# schematic.net
KiCad netlist of a schematic drawn in EAGLE
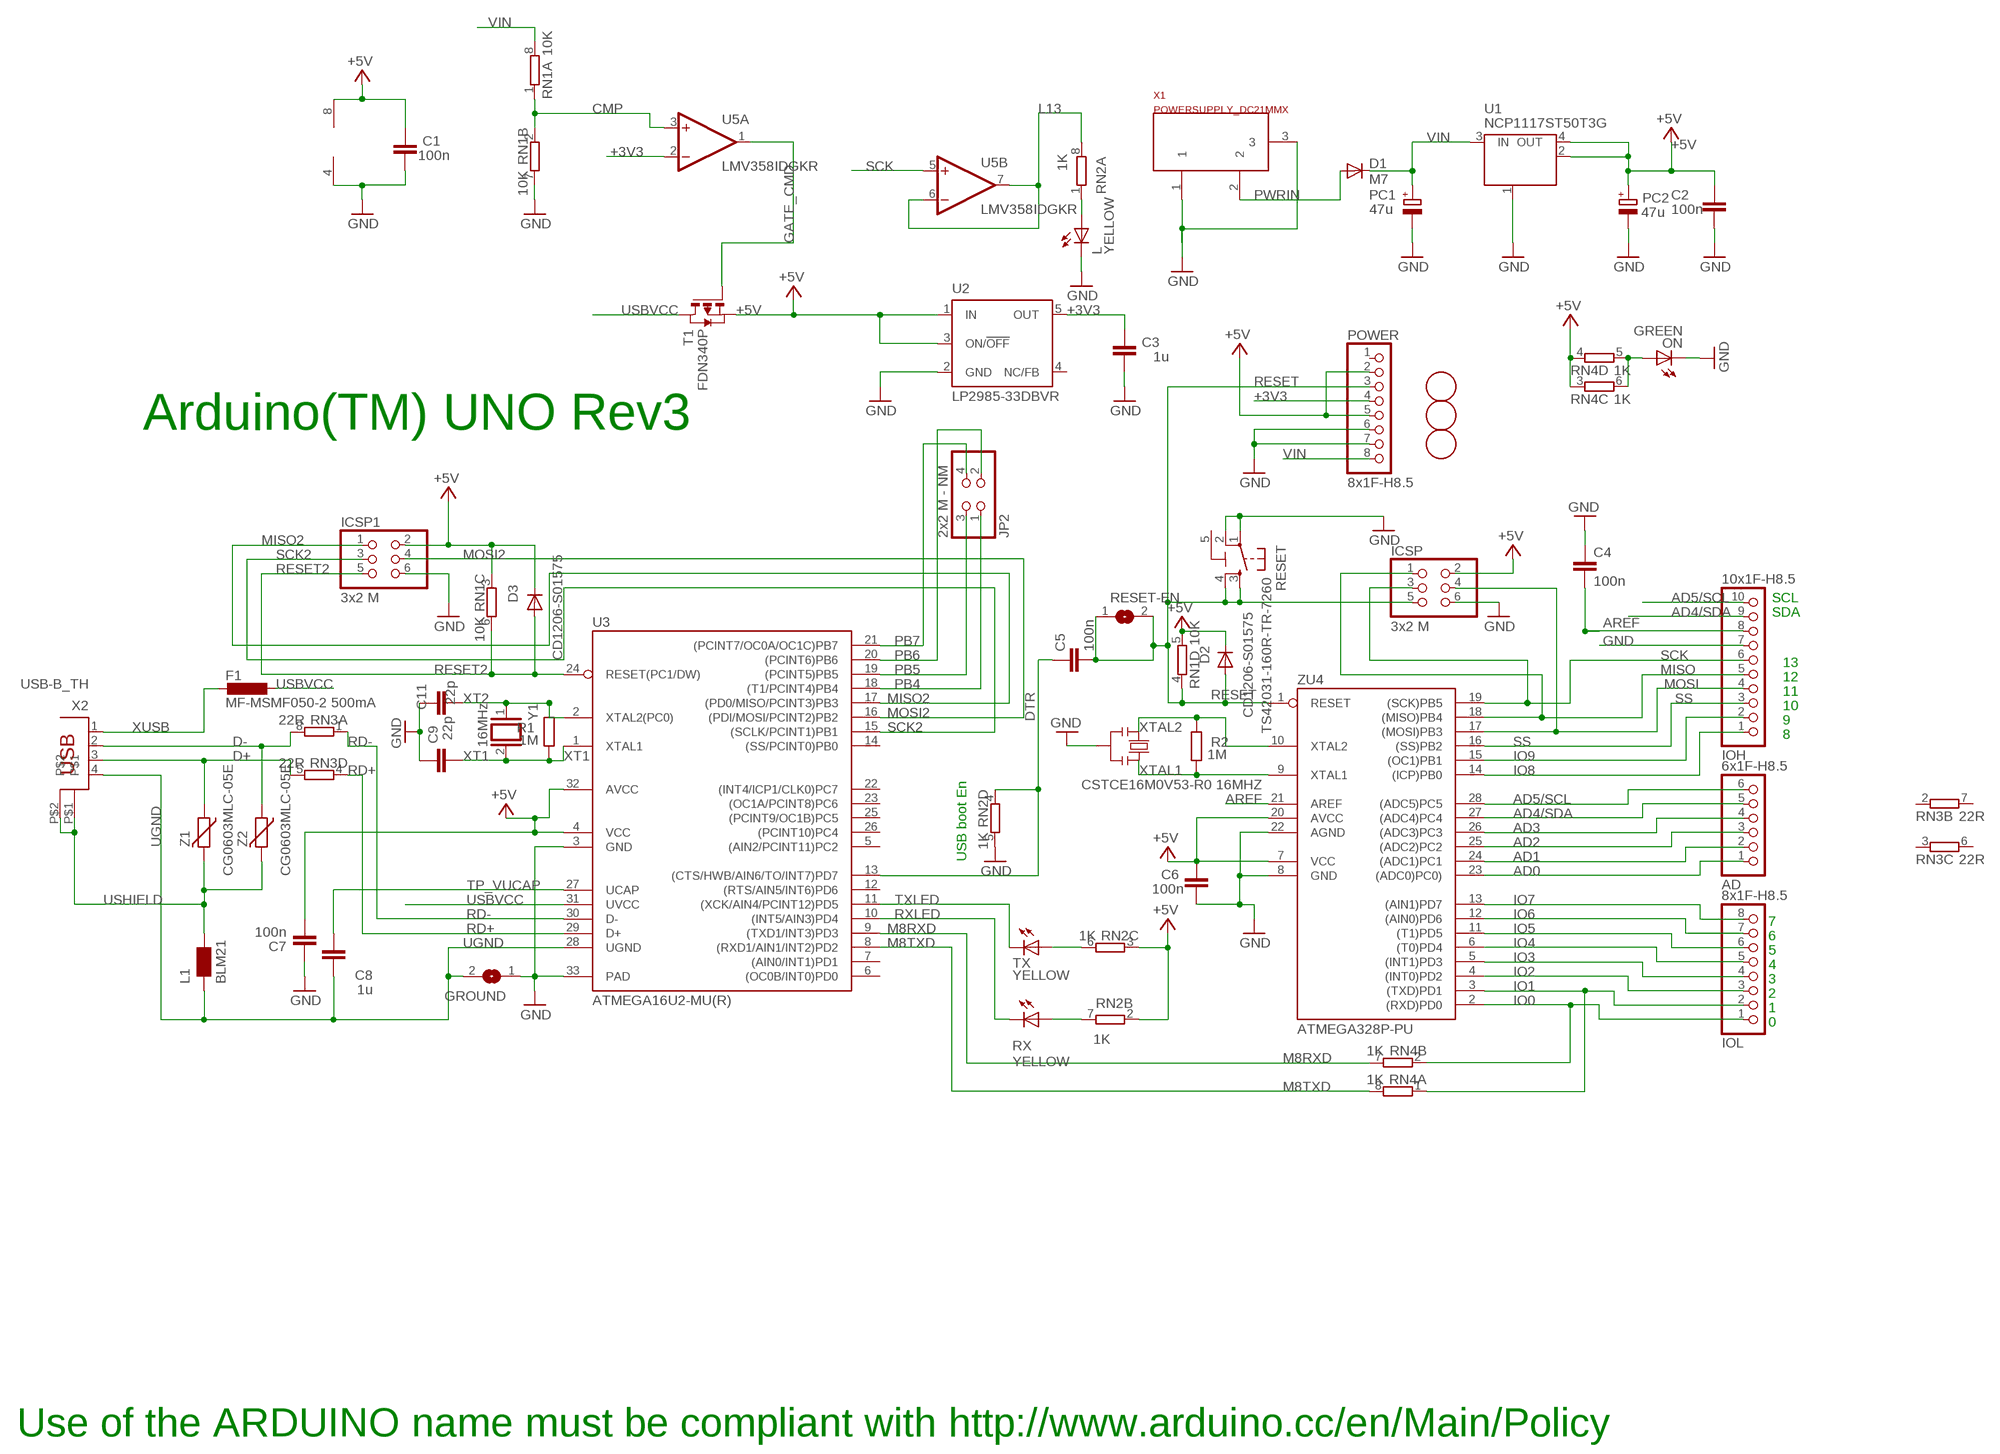
[diagram p0: schematic, sheet 1]

(export (version "E")
  (design (tool "Eeschema 10.0.6"))
  (components
    (comp (ref "AD")
      (value "6x1F-H8.5")
      (footprint "eagle-import:1X06")
      (libsource (lib "eagle-import") (part "PINHD-1X6"))
    )
    (comp (ref "C1")
      (value "100n")
      (footprint "eagle-import:C0603-ROUND")
      (libsource (lib "eagle-import") (part "C-EU0603-RND"))
    )
    (comp (ref "C2")
      (value "100n")
      (footprint "eagle-import:C0603-ROUND")
      (libsource (lib "eagle-import") (part "C-EU0603-RND"))
    )
    (comp (ref "C3")
      (value "1u")
      (footprint "eagle-import:C0603-ROUND")
      (libsource (lib "eagle-import") (part "C-EU0603-RND"))
    )
    (comp (ref "C4")
      (value "100n")
      (footprint "eagle-import:C0603-ROUND")
      (libsource (lib "eagle-import") (part "C-EU0603-RND"))
    )
    (comp (ref "C5")
      (value "100n")
      (footprint "eagle-import:C0603-ROUND")
      (libsource (lib "eagle-import") (part "C-EU0603-RND"))
    )
    (comp (ref "C6")
      (value "100n")
      (footprint "eagle-import:C0603-ROUND")
      (libsource (lib "eagle-import") (part "C-EU0603-RND"))
    )
    (comp (ref "C7")
      (value "100n")
      (footprint "eagle-import:C0603-ROUND")
      (libsource (lib "eagle-import") (part "C-EU0603-RND"))
    )
    (comp (ref "C8")
      (value "1u")
      (footprint "eagle-import:C0603-ROUND")
      (libsource (lib "eagle-import") (part "C-EU0603-RND"))
    )
    (comp (ref "C9")
      (value "22p")
      (footprint "eagle-import:C0603-ROUND")
      (libsource (lib "eagle-import") (part "C-EU0603-RND"))
    )
    (comp (ref "C11")
      (value "22p")
      (footprint "eagle-import:C0603-ROUND")
      (libsource (lib "eagle-import") (part "C-EU0603-RND"))
    )
    (comp (ref "D1")
      (value "M7")
      (footprint "eagle-import:SMB")
      (libsource (lib "eagle-import") (part "DIODE-SMB"))
    )
    (comp (ref "D2")
      (value "CD1206-S01575")
      (footprint "eagle-import:MINIMELF")
      (libsource (lib "eagle-import") (part "DIODE-MINIMELF"))
    )
    (comp (ref "D3")
      (value "CD1206-S01575")
      (footprint "eagle-import:MINIMELF")
      (libsource (lib "eagle-import") (part "DIODE-MINIMELF"))
    )
    (comp (ref "F1")
      (value "MF-MSMF050-2 500mA")
      (footprint "eagle-import:L1812")
      (libsource (lib "eagle-import") (part "L-EUL1812"))
    )
    (comp (ref "FD1")
      (value "FIDUCIALMOUNT")
      (footprint "eagle-import:FIDUCIA-MOUNT")
      (libsource (lib "eagle-import") (part "FIDUCIALMOUNT"))
    )
    (comp (ref "FD2")
      (value "FIDUCIALMOUNT")
      (footprint "eagle-import:FIDUCIA-MOUNT")
      (libsource (lib "eagle-import") (part "FIDUCIALMOUNT"))
    )
    (comp (ref "FD3")
      (value "FIDUCIALMOUNT")
      (footprint "eagle-import:FIDUCIA-MOUNT")
      (libsource (lib "eagle-import") (part "FIDUCIALMOUNT"))
    )
    (comp (ref "GROUND")
      (value "SJ")
      (footprint "eagle-import:SJ")
      (libsource (lib "eagle-import") (part "SJ"))
    )
    (comp (ref "ICSP")
      (value "3x2 M")
      (footprint "eagle-import:2X03")
      (libsource (lib "eagle-import") (part "PINHD-2X3"))
    )
    (comp (ref "ICSP1")
      (value "3x2 M")
      (footprint "eagle-import:2X03")
      (libsource (lib "eagle-import") (part "PINHD-2X3"))
    )
    (comp (ref "IOH")
      (value "10x1F-H8.5")
      (footprint "eagle-import:1X10")
      (libsource (lib "eagle-import") (part "PINHD-1X10_ARD"))
    )
    (comp (ref "IOL")
      (value "8x1F-H8.5")
      (footprint "eagle-import:1X08")
      (libsource (lib "eagle-import") (part "PINHD-1X8"))
    )
    (comp (ref "JP2")
      (value "2x2 M - NM")
      (footprint "eagle-import:2X02")
      (libsource (lib "eagle-import") (part "PINHD-2X2"))
    )
    (comp (ref "L")
      (value "YELLOW")
      (footprint "eagle-import:CHIP-LED0805")
      (libsource (lib "eagle-import") (part "LEDCHIP-LED0805"))
    )
    (comp (ref "L1")
      (value "BLM21")
      (footprint "eagle-import:0805")
      (libsource (lib "eagle-import") (part "WE-CBF_0805"))
    )
    (comp (ref "ON")
      (value "GREEN")
      (footprint "eagle-import:CHIP-LED0805")
      (libsource (lib "eagle-import") (part "LEDCHIP-LED0805"))
    )
    (comp (ref "PC1")
      (value "47u")
      (footprint "eagle-import:PANASONIC_D")
      (libsource (lib "eagle-import") (part "CPOL-EUD"))
    )
    (comp (ref "PC2")
      (value "47u")
      (footprint "eagle-import:PANASONIC_D")
      (libsource (lib "eagle-import") (part "CPOL-EUD"))
    )
    (comp (ref "POWER")
      (value "8x1F-H8.5")
      (footprint "eagle-import:1X08")
      (libsource (lib "eagle-import") (part "PINHD-1X8"))
    )
    (comp (ref "R1")
      (value "1M")
      (footprint "eagle-import:R0603-ROUND")
      (libsource (lib "eagle-import") (part "R-EU_R0603"))
    )
    (comp (ref "R2")
      (value "1M")
      (footprint "eagle-import:R0603-ROUND")
      (libsource (lib "eagle-import") (part "R-EU_R0603"))
    )
    (comp (ref "RESET")
      (value "TS42031-160R-TR-7260")
      (footprint "eagle-import:TS42")
      (libsource (lib "eagle-import") (part "TS42"))
    )
    (comp (ref "RESET-EN")
      (value "SJ")
      (footprint "eagle-import:SJ")
      (libsource (lib "eagle-import") (part "SJ"))
    )
    (comp (ref "RN1")
      (value "10K")
      (footprint "eagle-import:CAY16")
      (libsource (lib "eagle-import") (part "4R-NCAY16"))
    )
    (comp (ref "RN2")
      (value "1K")
      (footprint "eagle-import:CAY16")
      (libsource (lib "eagle-import") (part "4R-NCAY16"))
    )
    (comp (ref "RN3")
      (value "22R")
      (footprint "eagle-import:CAY16")
      (libsource (lib "eagle-import") (part "4R-NCAY16"))
    )
    (comp (ref "RN4")
      (value "1K")
      (footprint "eagle-import:CAY16")
      (libsource (lib "eagle-import") (part "4R-NCAY16"))
    )
    (comp (ref "RX")
      (value "YELLOW")
      (footprint "eagle-import:CHIP-LED0805")
      (libsource (lib "eagle-import") (part "LEDCHIP-LED0805"))
    )
    (comp (ref "T1")
      (value "FDN340P")
      (footprint "eagle-import:SOT-23")
      (libsource (lib "eagle-import") (part "PMOSSOT23"))
    )
    (comp (ref "TX")
      (value "YELLOW")
      (footprint "eagle-import:CHIP-LED0805")
      (libsource (lib "eagle-import") (part "LEDCHIP-LED0805"))
    )
    (comp (ref "U1")
      (value "NCP1117ST50T3G")
      (footprint "eagle-import:SOT223")
      (libsource (lib "eagle-import") (part "MC33269ST-3.3T3"))
    )
    (comp (ref "U2")
      (value "LP2985-33DBVR")
      (footprint "eagle-import:SOT23-DBV")
      (libsource (lib "eagle-import") (part "LP2985-XXDBVR33"))
    )
    (comp (ref "U3")
      (value "ATMEGA16U2-MU(R)")
      (footprint "eagle-import:MLF32")
      (libsource (lib "eagle-import") (part "ATMEGA16U2-MU"))
    )
    (comp (ref "U5")
      (value "LMV358IDGKR")
      (footprint "eagle-import:MSOP08")
      (libsource (lib "eagle-import") (part "LMV358?MMX"))
    )
    (comp (ref "X1")
      (value "POWERSUPPLY_DC21MMX")
      (footprint "eagle-import:POWERSUPPLY_DC-21MM")
      (libsource (lib "eagle-import") (part "POWERSUPPLY_DC21MMX"))
    )
    (comp (ref "X2")
      (value "USB-B_TH")
      (footprint "eagle-import:PN61729")
      (libsource (lib "eagle-import") (part "PN61729"))
    )
    (comp (ref "Y1")
      (value "16MHz")
      (footprint "eagle-import:QS")
      (libsource (lib "eagle-import") (part "XTAL/S"))
    )
    (comp (ref "Y2")
      (value "CSTCE16M0V53-R0 16MHZ")
      (footprint "eagle-import:RESONATOR")
      (libsource (lib "eagle-import") (part "RESONATORMU"))
    )
    (comp (ref "Z1")
      (value "CG0603MLC-05E")
      (footprint "eagle-import:CT_CN0603")
      (libsource (lib "eagle-import") (part "VARISTORCN0603"))
    )
    (comp (ref "Z2")
      (value "CG0603MLC-05E")
      (footprint "eagle-import:CT_CN0603")
      (libsource (lib "eagle-import") (part "VARISTORCN0603"))
    )
    (comp (ref "ZU4")
      (value "ATMEGA328P-PU")
      (footprint "eagle-import:DIL28-3")
      (libsource (lib "eagle-import") (part "ATMEGA328P-PU"))
    )
  )
  (nets
    (net (code "1") (name "+5V") (class "Default")
      (node (ref "C1") (pin "2") (pinfunction "2_2") (pintype "passive"))
      (node (ref "C2") (pin "2") (pinfunction "2_2") (pintype "passive"))
      (node (ref "C6") (pin "2") (pinfunction "2_2") (pintype "passive"))
      (node (ref "C7") (pin "1") (pinfunction "1_1") (pintype "passive"))
      (node (ref "D2") (pin "C") (pinfunction "C_C") (pintype "passive"))
      (node (ref "D3") (pin "C") (pinfunction "C_C") (pintype "passive"))
      (node (ref "ICSP") (pin "2") (pinfunction "2_2") (pintype "passive"))
      (node (ref "ICSP1") (pin "2") (pinfunction "2_2") (pintype "passive"))
      (node (ref "PC2") (pin "+") (pinfunction "+_+") (pintype "passive"))
      (node (ref "POWER") (pin "2") (pinfunction "2_2") (pintype "passive"))
      (node (ref "POWER") (pin "5") (pinfunction "5_5") (pintype "passive"))
      (node (ref "RN1") (pin "3") (pinfunction "1_3") (pintype "passive"))
      (node (ref "RN1") (pin "5") (pinfunction "2_5") (pintype "passive"))
      (node (ref "RN2") (pin "2") (pinfunction "1_2") (pintype "passive"))
      (node (ref "RN2") (pin "3") (pinfunction "1_3") (pintype "passive"))
      (node (ref "RN4") (pin "3") (pinfunction "1_3") (pintype "passive"))
      (node (ref "RN4") (pin "4") (pinfunction "1_4") (pintype "passive"))
      (node (ref "T1") (pin "2") (pinfunction "S_2") (pintype "passive"))
      (node (ref "U1") (pin "2") (pinfunction "OUT_2") (pintype "passive"))
      (node (ref "U1") (pin "4") (pinfunction "OUT_4") (pintype "passive"))
      (node (ref "U2") (pin "1") (pinfunction "IN_1") (pintype "input"))
      (node (ref "U2") (pin "3") (pinfunction "ON/~{OFF}_3") (pintype "input"))
      (node (ref "U3") (pin "32") (pinfunction "AVCC_32") (pintype "power_in"))
      (node (ref "U3") (pin "4") (pinfunction "VCC_4") (pintype "power_in"))
      (node (ref "U5") (pin "8") (pinfunction "V+_8") (pintype "power_in"))
      (node (ref "ZU4") (pin "20") (pinfunction "AVCC_20") (pintype "power_in"))
      (node (ref "ZU4") (pin "7") (pinfunction "VCC_7") (pintype "power_in"))
    )
    (net (code "2") (name "/+3V3") (class "Default")
      (node (ref "C3") (pin "2") (pinfunction "2_2") (pintype "passive"))
      (node (ref "POWER") (pin "4") (pinfunction "4_4") (pintype "passive"))
      (node (ref "U2") (pin "5") (pinfunction "OUT_5") (pintype "passive"))
      (node (ref "U5") (pin "2") (pinfunction "-IN_2") (pintype "input"))
    )
    (net (code "3") (name "/5-GND") (class "Default")
      (node (ref "RESET") (pin "5") (pinfunction "5-GND_5") (pintype "power_in"))
    )
    (net (code "4") (name "/AD0") (class "Default")
      (node (ref "AD") (pin "1") (pinfunction "1_1") (pintype "passive"))
      (node (ref "ZU4") (pin "23") (pinfunction "(ADC0)PC0)_23") (pintype "bidirectional"))
    )
    (net (code "5") (name "/AD1") (class "Default")
      (node (ref "AD") (pin "2") (pinfunction "2_2") (pintype "passive"))
      (node (ref "ZU4") (pin "24") (pinfunction "(ADC1)PC1_24") (pintype "bidirectional"))
    )
    (net (code "6") (name "/AD2") (class "Default")
      (node (ref "AD") (pin "3") (pinfunction "3_3") (pintype "passive"))
      (node (ref "ZU4") (pin "25") (pinfunction "(ADC2)PC2_25") (pintype "bidirectional"))
    )
    (net (code "7") (name "/AD3") (class "Default")
      (node (ref "AD") (pin "4") (pinfunction "4_4") (pintype "passive"))
      (node (ref "ZU4") (pin "26") (pinfunction "(ADC3)PC3_26") (pintype "bidirectional"))
    )
    (net (code "8") (name "/AD4{slash}SDA") (class "Default")
      (node (ref "AD") (pin "5") (pinfunction "5_5") (pintype "passive"))
      (node (ref "IOH") (pin "9") (pinfunction "9_9") (pintype "passive"))
      (node (ref "ZU4") (pin "27") (pinfunction "(ADC4)PC4_27") (pintype "bidirectional"))
    )
    (net (code "9") (name "/AD5{slash}SCL") (class "Default")
      (node (ref "AD") (pin "6") (pinfunction "6_6") (pintype "passive"))
      (node (ref "IOH") (pin "10") (pinfunction "10_10") (pintype "passive"))
      (node (ref "ZU4") (pin "28") (pinfunction "(ADC5)PC5_28") (pintype "bidirectional"))
    )
    (net (code "10") (name "/AREF") (class "Default")
      (node (ref "C4") (pin "2") (pinfunction "2_2") (pintype "passive"))
      (node (ref "IOH") (pin "8") (pinfunction "8_8") (pintype "passive"))
      (node (ref "ZU4") (pin "21") (pinfunction "AREF_21") (pintype "passive"))
    )
    (net (code "11") (name "/CMP") (class "Default")
      (node (ref "RN1") (pin "1") (pinfunction "1_1") (pintype "passive"))
      (node (ref "RN1") (pin "2") (pinfunction "1_2") (pintype "passive"))
      (node (ref "U5") (pin "3") (pinfunction "+IN_3") (pintype "input"))
    )
    (net (code "12") (name "/D+") (class "Default")
      (node (ref "RN3") (pin "5") (pinfunction "2_5") (pintype "passive"))
      (node (ref "X2") (pin "3") (pinfunction "3_3") (pintype "bidirectional"))
      (node (ref "Z1") (pin "1") (pinfunction "1_1") (pintype "passive"))
    )
    (net (code "13") (name "/D-") (class "Default")
      (node (ref "RN3") (pin "8") (pinfunction "2_8") (pintype "passive"))
      (node (ref "X2") (pin "2") (pinfunction "2_2") (pintype "bidirectional"))
      (node (ref "Z2") (pin "1") (pinfunction "1_1") (pintype "passive"))
    )
    (net (code "14") (name "/DTR") (class "Default")
      (node (ref "C5") (pin "1") (pinfunction "1_1") (pintype "passive"))
      (node (ref "RN2") (pin "4") (pinfunction "1_4") (pintype "passive"))
      (node (ref "U3") (pin "13") (pinfunction "(CTS/HWB/AIN6/TO/INT7)PD7_13") (pintype "bidirectional"))
    )
    (net (code "15") (name "/GATE_CMD") (class "Default")
      (node (ref "T1") (pin "3") (pinfunction "G_3") (pintype "passive"))
      (node (ref "U5") (pin "1") (pinfunction "OUT_1") (pintype "output"))
    )
    (net (code "16") (name "/IO0") (class "Default")
      (node (ref "IOL") (pin "1") (pinfunction "1_1") (pintype "passive"))
      (node (ref "RN4") (pin "2") (pinfunction "1_2") (pintype "passive"))
      (node (ref "ZU4") (pin "2") (pinfunction "(RXD)PD0_2") (pintype "bidirectional"))
    )
    (net (code "17") (name "/IO1") (class "Default")
      (node (ref "IOL") (pin "2") (pinfunction "2_2") (pintype "passive"))
      (node (ref "RN4") (pin "1") (pinfunction "1_1") (pintype "passive"))
      (node (ref "ZU4") (pin "3") (pinfunction "(TXD)PD1_3") (pintype "bidirectional"))
    )
    (net (code "18") (name "/IO2") (class "Default")
      (node (ref "IOL") (pin "3") (pinfunction "3_3") (pintype "passive"))
      (node (ref "ZU4") (pin "4") (pinfunction "(INT0)PD2_4") (pintype "bidirectional"))
    )
    (net (code "19") (name "/IO3") (class "Default")
      (node (ref "IOL") (pin "4") (pinfunction "4_4") (pintype "passive"))
      (node (ref "ZU4") (pin "5") (pinfunction "(INT1)PD3_5") (pintype "bidirectional"))
    )
    (net (code "20") (name "/IO4") (class "Default")
      (node (ref "IOL") (pin "5") (pinfunction "5_5") (pintype "passive"))
      (node (ref "ZU4") (pin "6") (pinfunction "(T0)PD4_6") (pintype "bidirectional"))
    )
    (net (code "21") (name "/IO5") (class "Default")
      (node (ref "IOL") (pin "6") (pinfunction "6_6") (pintype "passive"))
      (node (ref "ZU4") (pin "11") (pinfunction "(T1)PD5_11") (pintype "bidirectional"))
    )
    (net (code "22") (name "/IO6") (class "Default")
      (node (ref "IOL") (pin "7") (pinfunction "7_7") (pintype "passive"))
      (node (ref "ZU4") (pin "12") (pinfunction "(AIN0)PD6_12") (pintype "bidirectional"))
    )
    (net (code "23") (name "/IO7") (class "Default")
      (node (ref "IOL") (pin "8") (pinfunction "8_8") (pintype "passive"))
      (node (ref "ZU4") (pin "13") (pinfunction "(AIN1)PD7_13") (pintype "bidirectional"))
    )
    (net (code "24") (name "/IO8") (class "Default")
      (node (ref "IOH") (pin "1") (pinfunction "1_1") (pintype "passive"))
      (node (ref "ZU4") (pin "14") (pinfunction "(ICP)PB0_14") (pintype "bidirectional"))
    )
    (net (code "25") (name "/IO9") (class "Default")
      (node (ref "IOH") (pin "2") (pinfunction "2_2") (pintype "passive"))
      (node (ref "ZU4") (pin "15") (pinfunction "(OC1)PB1_15") (pintype "bidirectional"))
    )
    (net (code "26") (name "/L13") (class "Default")
      (node (ref "RN2") (pin "8") (pinfunction "2_8") (pintype "passive"))
      (node (ref "U5") (pin "6") (pinfunction "-IN_6") (pintype "input"))
      (node (ref "U5") (pin "7") (pinfunction "OUT_7") (pintype "output"))
    )
    (net (code "27") (name "/M8RXD") (class "Default")
      (node (ref "RN4") (pin "7") (pinfunction "2_7") (pintype "passive"))
      (node (ref "U3") (pin "9") (pinfunction "(TXD1/INT3)PD3_9") (pintype "bidirectional"))
    )
    (net (code "28") (name "/M8TXD") (class "Default")
      (node (ref "RN4") (pin "8") (pinfunction "2_8") (pintype "passive"))
      (node (ref "U3") (pin "8") (pinfunction "(RXD1/AIN1/INT2)PD2_8") (pintype "bidirectional"))
    )
    (net (code "29") (name "/MISO") (class "Default")
      (node (ref "ICSP") (pin "1") (pinfunction "1_1") (pintype "passive"))
      (node (ref "IOH") (pin "5") (pinfunction "5_5") (pintype "passive"))
      (node (ref "ZU4") (pin "18") (pinfunction "(MISO)PB4_18") (pintype "bidirectional"))
    )
    (net (code "30") (name "/MISO2") (class "Default")
      (node (ref "ICSP1") (pin "1") (pinfunction "1_1") (pintype "passive"))
      (node (ref "U3") (pin "17") (pinfunction "(PD0/MISO/PCINT3)PB3_17") (pintype "bidirectional"))
    )
    (net (code "31") (name "/MOSI") (class "Default")
      (node (ref "ICSP") (pin "4") (pinfunction "4_4") (pintype "passive"))
      (node (ref "IOH") (pin "4") (pinfunction "4_4") (pintype "passive"))
      (node (ref "ZU4") (pin "17") (pinfunction "(MOSI)PB3_17") (pintype "bidirectional"))
    )
    (net (code "32") (name "/MOSI2") (class "Default")
      (node (ref "ICSP1") (pin "4") (pinfunction "4_4") (pintype "passive"))
      (node (ref "U3") (pin "16") (pinfunction "(PDI/MOSI/PCINT2)PB2_16") (pintype "bidirectional"))
    )
    (net (code "33") (name "/PB4") (class "Default")
      (node (ref "JP2") (pin "1") (pinfunction "1_1") (pintype "passive"))
      (node (ref "U3") (pin "18") (pinfunction "(T1/PCINT4)PB4_18") (pintype "bidirectional"))
    )
    (net (code "34") (name "/PB5") (class "Default")
      (node (ref "JP2") (pin "3") (pinfunction "3_3") (pintype "passive"))
      (node (ref "U3") (pin "19") (pinfunction "(PCINT5)PB5_19") (pintype "bidirectional"))
    )
    (net (code "35") (name "/PB6") (class "Default")
      (node (ref "JP2") (pin "2") (pinfunction "2_2") (pintype "passive"))
      (node (ref "U3") (pin "20") (pinfunction "(PCINT6)PB6_20") (pintype "bidirectional"))
    )
    (net (code "36") (name "/PB7") (class "Default")
      (node (ref "JP2") (pin "4") (pinfunction "4_4") (pintype "passive"))
      (node (ref "U3") (pin "21") (pinfunction "(PCINT7/OC0A/OC1C)PB7_21") (pintype "bidirectional"))
    )
    (net (code "37") (name "/PWRIN") (class "Default")
      (node (ref "D1") (pin "A") (pinfunction "A_A") (pintype "passive"))
      (node (ref "X1") (pin "2") (pinfunction "2_2") (pintype "power_in"))
    )
    (net (code "38") (name "/RD+") (class "Default")
      (node (ref "RN3") (pin "4") (pinfunction "1_4") (pintype "passive"))
      (node (ref "U3") (pin "29") (pinfunction "D+_29") (pintype "bidirectional"))
    )
    (net (code "39") (name "/RD-") (class "Default")
      (node (ref "RN3") (pin "1") (pinfunction "1_1") (pintype "passive"))
      (node (ref "U3") (pin "30") (pinfunction "D-_30") (pintype "bidirectional"))
    )
    (net (code "40") (name "/RESET") (class "Default")
      (node (ref "C5") (pin "2") (pinfunction "2_2") (pintype "passive"))
      (node (ref "D2") (pin "A") (pinfunction "A_A") (pintype "passive"))
      (node (ref "ICSP") (pin "5") (pinfunction "5_5") (pintype "passive"))
      (node (ref "POWER") (pin "3") (pinfunction "3_3") (pintype "passive"))
      (node (ref "RESET") (pin "3") (pinfunction "3_3") (pintype "passive"))
      (node (ref "RESET") (pin "4") (pinfunction "4_4") (pintype "passive"))
      (node (ref "RESET-EN") (pin "1") (pinfunction "1_1") (pintype "passive"))
      (node (ref "RESET-EN") (pin "2") (pinfunction "2_2") (pintype "passive"))
      (node (ref "RN1") (pin "4") (pinfunction "1_4") (pintype "passive"))
      (node (ref "ZU4") (pin "1") (pinfunction "RESET_1") (pintype "input"))
    )
    (net (code "41") (name "/RESET2") (class "Default")
      (node (ref "D3") (pin "A") (pinfunction "A_A") (pintype "passive"))
      (node (ref "ICSP1") (pin "5") (pinfunction "5_5") (pintype "passive"))
      (node (ref "RN1") (pin "6") (pinfunction "2_6") (pintype "passive"))
      (node (ref "U3") (pin "24") (pinfunction "RESET(PC1/DW)_24") (pintype "input"))
    )
    (net (code "42") (name "/RXLED") (class "Default")
      (node (ref "RX") (pin "C") (pinfunction "C_C") (pintype "passive"))
      (node (ref "U3") (pin "10") (pinfunction "(INT5/AIN3)PD4_10") (pintype "bidirectional"))
    )
    (net (code "43") (name "/SCK") (class "Default")
      (node (ref "ICSP") (pin "3") (pinfunction "3_3") (pintype "passive"))
      (node (ref "IOH") (pin "6") (pinfunction "6_6") (pintype "passive"))
      (node (ref "U5") (pin "5") (pinfunction "+IN_5") (pintype "input"))
      (node (ref "ZU4") (pin "19") (pinfunction "(SCK)PB5_19") (pintype "bidirectional"))
    )
    (net (code "44") (name "/SCK2") (class "Default")
      (node (ref "ICSP1") (pin "3") (pinfunction "3_3") (pintype "passive"))
      (node (ref "U3") (pin "15") (pinfunction "(SCLK/PCINT1)PB1_15") (pintype "bidirectional"))
    )
    (net (code "45") (name "/SS") (class "Default")
      (node (ref "IOH") (pin "3") (pinfunction "3_3") (pintype "passive"))
      (node (ref "ZU4") (pin "16") (pinfunction "(SS)PB2_16") (pintype "bidirectional"))
    )
    (net (code "46") (name "/TP_VUCAP") (class "Default")
      (node (ref "C8") (pin "1") (pinfunction "1_1") (pintype "passive"))
      (node (ref "U3") (pin "27") (pinfunction "UCAP_27") (pintype "passive"))
    )
    (net (code "47") (name "/TXLED") (class "Default")
      (node (ref "TX") (pin "C") (pinfunction "C_C") (pintype "passive"))
      (node (ref "U3") (pin "11") (pinfunction "(XCK/AIN4/PCINT12)PD5_11") (pintype "bidirectional"))
    )
    (net (code "48") (name "/UGND") (class "Default")
      (node (ref "C8") (pin "2") (pinfunction "2_2") (pintype "passive"))
      (node (ref "GROUND") (pin "2") (pinfunction "2_2") (pintype "passive"))
      (node (ref "L1") (pin "1") (pinfunction "1_1") (pintype "passive"))
      (node (ref "U3") (pin "28") (pinfunction "UGND_28") (pintype "power_in"))
      (node (ref "X2") (pin "4") (pinfunction "4_4") (pintype "bidirectional"))
    )
    (net (code "49") (name "/USBVCC") (class "Default")
      (node (ref "F1") (pin "1") (pinfunction "1_1") (pintype "passive"))
      (node (ref "T1") (pin "1") (pinfunction "D_1") (pintype "passive"))
      (node (ref "U3") (pin "31") (pinfunction "UVCC_31") (pintype "power_in"))
    )
    (net (code "50") (name "/USHIELD") (class "Default")
      (node (ref "L1") (pin "2") (pinfunction "2_2") (pintype "passive"))
      (node (ref "X2") (pin "P$1") (pinfunction "P$1_P$1") (pintype "bidirectional"))
      (node (ref "X2") (pin "P$2") (pinfunction "P$2_P$2") (pintype "bidirectional"))
      (node (ref "Z1") (pin "2") (pinfunction "2_2") (pintype "passive"))
      (node (ref "Z2") (pin "2") (pinfunction "2_2") (pintype "passive"))
    )
    (net (code "51") (name "/VIN") (class "Default")
      (node (ref "D1") (pin "C") (pinfunction "C_C") (pintype "passive"))
      (node (ref "PC1") (pin "+") (pinfunction "+_+") (pintype "passive"))
      (node (ref "POWER") (pin "8") (pinfunction "8_8") (pintype "passive"))
      (node (ref "RN1") (pin "8") (pinfunction "2_8") (pintype "passive"))
      (node (ref "U1") (pin "3") (pinfunction "IN_3") (pintype "input"))
    )
    (net (code "52") (name "/XT1") (class "Default")
      (node (ref "C9") (pin "1") (pinfunction "1_1") (pintype "passive"))
      (node (ref "R1") (pin "1") (pinfunction "1_1") (pintype "passive"))
      (node (ref "U3") (pin "1") (pinfunction "XTAL1_1") (pintype "bidirectional"))
      (node (ref "Y1") (pin "2") (pinfunction "2_2") (pintype "passive"))
    )
    (net (code "53") (name "/XT2") (class "Default")
      (node (ref "C11") (pin "1") (pinfunction "1_1") (pintype "passive"))
      (node (ref "R1") (pin "2") (pinfunction "2_2") (pintype "passive"))
      (node (ref "U3") (pin "2") (pinfunction "XTAL2(PC0)_2") (pintype "bidirectional"))
      (node (ref "Y1") (pin "1") (pinfunction "1_1") (pintype "passive"))
    )
    (net (code "54") (name "/XTAL1") (class "Default")
      (node (ref "R2") (pin "1") (pinfunction "1_1") (pintype "passive"))
      (node (ref "Y2") (pin "3") (pinfunction "3_3") (pintype "passive"))
      (node (ref "ZU4") (pin "9") (pinfunction "XTAL1_9") (pintype "bidirectional"))
    )
    (net (code "55") (name "/XTAL2") (class "Default")
      (node (ref "R2") (pin "2") (pinfunction "2_2") (pintype "passive"))
      (node (ref "Y2") (pin "1") (pinfunction "1_1") (pintype "passive"))
      (node (ref "ZU4") (pin "10") (pinfunction "XTAL2_10") (pintype "bidirectional"))
    )
    (net (code "56") (name "/XUSB") (class "Default")
      (node (ref "F1") (pin "2") (pinfunction "2_2") (pintype "passive"))
      (node (ref "X2") (pin "1") (pinfunction "1_1") (pintype "bidirectional"))
    )
    (net (code "57") (name "GND") (class "Default")
      (node (ref "C1") (pin "1") (pinfunction "1_1") (pintype "passive"))
      (node (ref "C11") (pin "2") (pinfunction "2_2") (pintype "passive"))
      (node (ref "C2") (pin "1") (pinfunction "1_1") (pintype "passive"))
      (node (ref "C3") (pin "1") (pinfunction "1_1") (pintype "passive"))
      (node (ref "C4") (pin "1") (pinfunction "1_1") (pintype "passive"))
      (node (ref "C6") (pin "1") (pinfunction "1_1") (pintype "passive"))
      (node (ref "C7") (pin "2") (pinfunction "2_2") (pintype "passive"))
      (node (ref "C9") (pin "2") (pinfunction "2_2") (pintype "passive"))
      (node (ref "GROUND") (pin "1") (pinfunction "1_1") (pintype "passive"))
      (node (ref "ICSP") (pin "6") (pinfunction "6_6") (pintype "passive"))
      (node (ref "ICSP1") (pin "6") (pinfunction "6_6") (pintype "passive"))
      (node (ref "IOH") (pin "7") (pinfunction "7_7") (pintype "passive"))
      (node (ref "L") (pin "C") (pinfunction "C_C") (pintype "passive"))
      (node (ref "ON") (pin "C") (pinfunction "C_C") (pintype "passive"))
      (node (ref "PC1") (pin "-") (pinfunction "-_-") (pintype "passive"))
      (node (ref "PC2") (pin "-") (pinfunction "-_-") (pintype "passive"))
      (node (ref "POWER") (pin "6") (pinfunction "6_6") (pintype "passive"))
      (node (ref "POWER") (pin "7") (pinfunction "7_7") (pintype "passive"))
      (node (ref "RESET") (pin "1") (pinfunction "1_1") (pintype "passive"))
      (node (ref "RESET") (pin "2") (pinfunction "2_2") (pintype "passive"))
      (node (ref "RN1") (pin "7") (pinfunction "2_7") (pintype "passive"))
      (node (ref "RN2") (pin "5") (pinfunction "2_5") (pintype "passive"))
      (node (ref "U1") (pin "1") (pinfunction "GND/ADJ_1") (pintype "input"))
      (node (ref "U2") (pin "2") (pinfunction "GND_2") (pintype "power_in"))
      (node (ref "U3") (pin "3") (pinfunction "GND_3") (pintype "power_in"))
      (node (ref "U3") (pin "33") (pinfunction "PAD_33") (pintype "power_in"))
      (node (ref "U5") (pin "4") (pinfunction "V-_4") (pintype "power_in"))
      (node (ref "X1") (pin "1") (pinfunction "1_1") (pintype "power_in"))
      (node (ref "X1") (pin "3") (pinfunction "3_3") (pintype "power_in"))
      (node (ref "Y2") (pin "2") (pinfunction "2_2") (pintype "passive"))
      (node (ref "ZU4") (pin "22") (pinfunction "AGND_22") (pintype "power_in"))
      (node (ref "ZU4") (pin "8") (pinfunction "GND_8") (pintype "power_in"))
    )
    (net (code "58") (name "Net-(L-PadA)") (class "Default")
      (node (ref "L") (pin "A") (pinfunction "A_A") (pintype "passive"))
      (node (ref "RN2") (pin "1") (pinfunction "1_1") (pintype "passive"))
    )
    (net (code "59") (name "Net-(RN2B-2)") (class "Default")
      (node (ref "RN2") (pin "7") (pinfunction "2_7") (pintype "passive"))
      (node (ref "RX") (pin "A") (pinfunction "A_A") (pintype "passive"))
    )
    (net (code "60") (name "Net-(RN2C-2)") (class "Default")
      (node (ref "RN2") (pin "6") (pinfunction "2_6") (pintype "passive"))
      (node (ref "TX") (pin "A") (pinfunction "A_A") (pintype "passive"))
    )
    (net (code "61") (name "Net-(RN4C-2)") (class "Default")
      (node (ref "ON") (pin "A") (pinfunction "A_A") (pintype "passive"))
      (node (ref "RN4") (pin "5") (pinfunction "2_5") (pintype "passive"))
      (node (ref "RN4") (pin "6") (pinfunction "2_6") (pintype "passive"))
    )
    (net (code "62") (name "unconnected-(POWER-Pad1)") (class "Default")
      (node (ref "POWER") (pin "1") (pinfunction "1_1") (pintype "passive"))
    )
    (net (code "63") (name "unconnected-(RN3B-1-Pad2)") (class "Default")
      (node (ref "RN3") (pin "2") (pinfunction "1_2") (pintype "passive"))
    )
    (net (code "64") (name "unconnected-(RN3B-2-Pad7)") (class "Default")
      (node (ref "RN3") (pin "7") (pinfunction "2_7") (pintype "passive"))
    )
    (net (code "65") (name "unconnected-(RN3C-1-Pad3)") (class "Default")
      (node (ref "RN3") (pin "3") (pinfunction "1_3") (pintype "passive"))
    )
    (net (code "66") (name "unconnected-(RN3C-2-Pad6)") (class "Default")
      (node (ref "RN3") (pin "6") (pinfunction "2_6") (pintype "passive"))
    )
    (net (code "67") (name "unconnected-(U2-NC{slash}FB-Pad4)") (class "Default")
      (node (ref "U2") (pin "4") (pinfunction "NC/FB_4") (pintype "passive"))
    )
    (net (code "68") (name "unconnected-(U3-(AIN0{slash}INT1)PD1-Pad7)") (class "Default")
      (node (ref "U3") (pin "7") (pinfunction "(AIN0/INT1)PD1_7") (pintype "bidirectional"))
    )
    (net (code "69") (name "unconnected-(U3-(AIN2{slash}PCINT11)PC2-Pad5)") (class "Default")
      (node (ref "U3") (pin "5") (pinfunction "(AIN2/PCINT11)PC2_5") (pintype "bidirectional"))
    )
    (net (code "70") (name "unconnected-(U3-(INT4{slash}ICP1{slash}CLK0)PC7-Pad22)") (class "Default")
      (node (ref "U3") (pin "22") (pinfunction "(INT4/ICP1/CLK0)PC7_22") (pintype "bidirectional"))
    )
    (net (code "71") (name "unconnected-(U3-(OC0B{slash}INT0)PD0-Pad6)") (class "Default")
      (node (ref "U3") (pin "6") (pinfunction "(OC0B/INT0)PD0_6") (pintype "bidirectional"))
    )
    (net (code "72") (name "unconnected-(U3-(OC1A{slash}PCINT8)PC6-Pad23)") (class "Default")
      (node (ref "U3") (pin "23") (pinfunction "(OC1A/PCINT8)PC6_23") (pintype "bidirectional"))
    )
    (net (code "73") (name "unconnected-(U3-(PCINT9{slash}OC1B)PC5-Pad25)") (class "Default")
      (node (ref "U3") (pin "25") (pinfunction "(PCINT9/OC1B)PC5_25") (pintype "bidirectional"))
    )
    (net (code "74") (name "unconnected-(U3-(PCINT10)PC4-Pad26)") (class "Default")
      (node (ref "U3") (pin "26") (pinfunction "(PCINT10)PC4_26") (pintype "bidirectional"))
    )
    (net (code "75") (name "unconnected-(U3-(RTS{slash}AIN5{slash}INT6)PD6-Pad12)") (class "Default")
      (node (ref "U3") (pin "12") (pinfunction "(RTS/AIN5/INT6)PD6_12") (pintype "bidirectional"))
    )
    (net (code "76") (name "unconnected-(U3-(SS{slash}PCINT0)PB0-Pad14)") (class "Default")
      (node (ref "U3") (pin "14") (pinfunction "(SS/PCINT0)PB0_14") (pintype "bidirectional"))
    )
  )
)
